# Schematic7.net
KiCad netlist of a schematic drawn in EAGLE
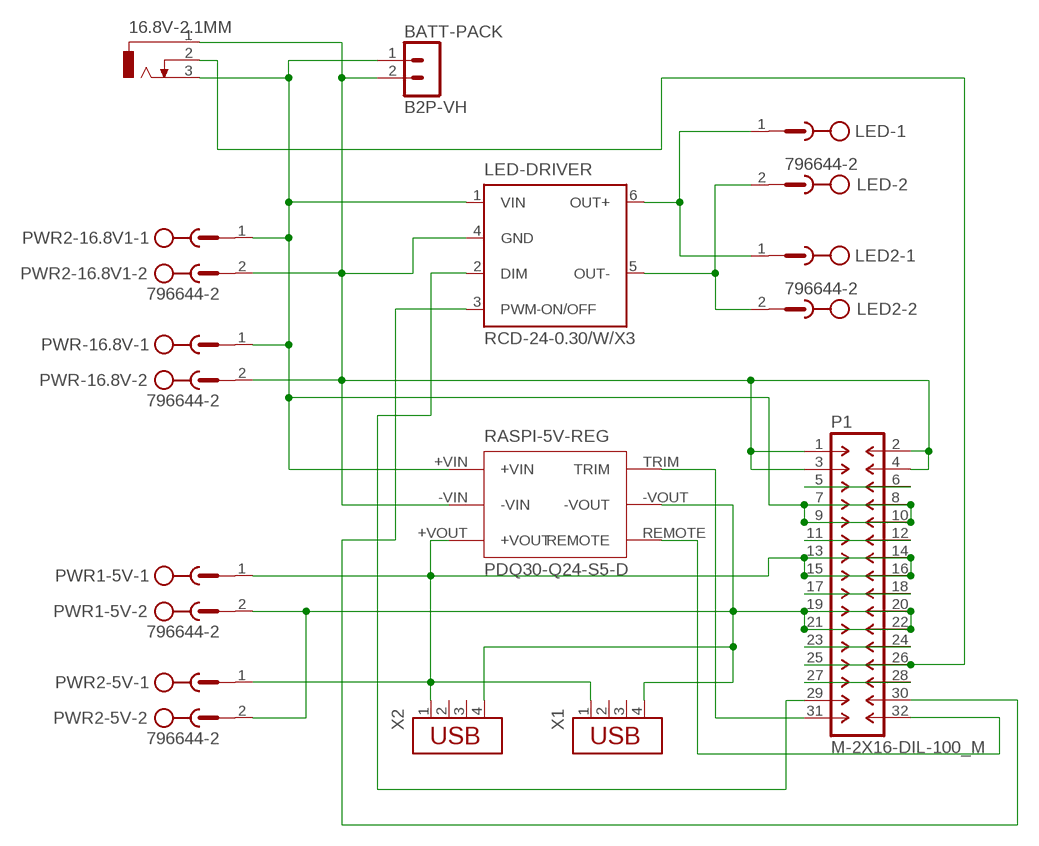
[diagram p0: schematic, sheet 1]

(export (version "E")
  (design (tool "Eeschema 10.0.6"))
  (components
    (comp (ref "16.8V-2.1MM")
      (value "DCJ0303")
      (footprint "eagle-import:DCJ0303")
      (libsource (lib "eagle-import") (part "DCJ0303"))
    )
    (comp (ref "BATT-PACK")
      (value "B2P-VH")
      (footprint "eagle-import:B2P-VH")
      (libsource (lib "eagle-import") (part "B2P-VH"))
    )
    (comp (ref "LED")
      (value "796644-2")
      (footprint "eagle-import:796644-2")
      (libsource (lib "eagle-import") (part "796644-2"))
    )
    (comp (ref "LED-DRIVER")
      (value "RCD-24-0.30/W/X3")
      (footprint "eagle-import:RCD-24_W_X3")
      (libsource (lib "eagle-import") (part "RCD-24/W/X3-0.30"))
    )
    (comp (ref "LED2")
      (value "796644-2")
      (footprint "eagle-import:796644-2")
      (libsource (lib "eagle-import") (part "796644-2"))
    )
    (comp (ref "P1")
      (value "M-2X16-DIL-100_M")
      (footprint "eagle-import:DIL-100-2X16_M")
      (libsource (lib "eagle-import") (part "M-2X16-DIL-100_M"))
    )
    (comp (ref "PWR-16.8V")
      (value "796644-2")
      (footprint "eagle-import:796644-2")
      (libsource (lib "eagle-import") (part "796644-2"))
    )
    (comp (ref "PWR1-5V")
      (value "796644-2")
      (footprint "eagle-import:796644-2")
      (libsource (lib "eagle-import") (part "796644-2"))
    )
    (comp (ref "PWR2-5V")
      (value "796644-2")
      (footprint "eagle-import:796644-2")
      (libsource (lib "eagle-import") (part "796644-2"))
    )
    (comp (ref "PWR2-16.8V1")
      (value "796644-2")
      (footprint "eagle-import:796644-2")
      (libsource (lib "eagle-import") (part "796644-2"))
    )
    (comp (ref "RASPI-5V-REG")
      (value "PDQ30-Q24-S5-D")
      (footprint "eagle-import:PDQ30-Q24-S5-D")
      (libsource (lib "eagle-import") (part "PDQ30-Q24-S5-D"))
    )
    (comp (ref "X1")
      (value "USB-787616")
      (footprint "eagle-import:USB")
      (libsource (lib "eagle-import") (part "USB-787616"))
    )
    (comp (ref "X2")
      (value "USB-787616")
      (footprint "eagle-import:USB")
      (libsource (lib "eagle-import") (part "USB-787616"))
    )
  )
  (nets
    (net (code "1") (name "Net-(16.8V-2.1MM-Pad2)") (class "Default")
      (node (ref "16.8V-2.1MM") (pin "2") (pinfunction "2_2") (pintype "passive"))
      (node (ref "P1") (pin "25") (pinfunction "25_25") (pintype "passive"))
      (node (ref "P1") (pin "26") (pinfunction "26_26") (pintype "passive"))
    )
    (net (code "2") (name "Net-(LED-DRIVER-DIM)") (class "Default")
      (node (ref "LED-DRIVER") (pin "2") (pinfunction "DIM_2") (pintype "passive"))
      (node (ref "P1") (pin "29") (pinfunction "29_29") (pintype "passive"))
    )
    (net (code "3") (name "Net-(LED-DRIVER-GND)") (class "Default")
      (node (ref "16.8V-2.1MM") (pin "1") (pinfunction "1_1") (pintype "passive"))
      (node (ref "BATT-PACK") (pin "2") (pinfunction "2_2") (pintype "passive"))
      (node (ref "LED-DRIVER") (pin "4") (pinfunction "GND_4") (pintype "power_in"))
      (node (ref "P1") (pin "1") (pinfunction "1_1") (pintype "passive"))
      (node (ref "P1") (pin "2") (pinfunction "2_2") (pintype "passive"))
      (node (ref "P1") (pin "3") (pinfunction "3_3") (pintype "passive"))
      (node (ref "P1") (pin "4") (pinfunction "4_4") (pintype "passive"))
      (node (ref "PWR-16.8V") (pin "2") (pinfunction "SK_2") (pintype "passive"))
      (node (ref "PWR2-16.8V1") (pin "2") (pinfunction "SK_2") (pintype "passive"))
      (node (ref "RASPI-5V-REG") (pin "-VIN") (pinfunction "-VIN_-VIN") (pintype "bidirectional"))
    )
    (net (code "4") (name "Net-(LED-DRIVER-OUT+)") (class "Default")
      (node (ref "LED") (pin "1") (pinfunction "SK_1") (pintype "passive"))
      (node (ref "LED-DRIVER") (pin "6") (pinfunction "OUT+_6") (pintype "output"))
      (node (ref "LED2") (pin "1") (pinfunction "SK_1") (pintype "passive"))
    )
    (net (code "5") (name "Net-(LED-DRIVER-OUT-)") (class "Default")
      (node (ref "LED") (pin "2") (pinfunction "SK_2") (pintype "passive"))
      (node (ref "LED-DRIVER") (pin "5") (pinfunction "OUT-_5") (pintype "output"))
      (node (ref "LED2") (pin "2") (pinfunction "SK_2") (pintype "passive"))
    )
    (net (code "6") (name "Net-(LED-DRIVER-PWM-ON{slash}OFF)") (class "Default")
      (node (ref "LED-DRIVER") (pin "3") (pinfunction "PWM-ON/OFF_3") (pintype "passive"))
      (node (ref "P1") (pin "30") (pinfunction "30_30") (pintype "passive"))
    )
    (net (code "7") (name "Net-(LED-DRIVER-VIN)") (class "Default")
      (node (ref "16.8V-2.1MM") (pin "3") (pinfunction "3_3") (pintype "passive"))
      (node (ref "BATT-PACK") (pin "1") (pinfunction "1_1") (pintype "passive"))
      (node (ref "LED-DRIVER") (pin "1") (pinfunction "VIN_1") (pintype "input"))
      (node (ref "P1") (pin "10") (pinfunction "10_10") (pintype "passive"))
      (node (ref "P1") (pin "7") (pinfunction "7_7") (pintype "passive"))
      (node (ref "P1") (pin "8") (pinfunction "8_8") (pintype "passive"))
      (node (ref "P1") (pin "9") (pinfunction "9_9") (pintype "passive"))
      (node (ref "PWR-16.8V") (pin "1") (pinfunction "SK_1") (pintype "passive"))
      (node (ref "PWR2-16.8V1") (pin "1") (pinfunction "SK_1") (pintype "passive"))
      (node (ref "RASPI-5V-REG") (pin "+VIN") (pinfunction "+VIN_+VIN") (pintype "bidirectional"))
    )
    (net (code "8") (name "Net-(P1-Pad5)") (class "Default")
      (node (ref "P1") (pin "5") (pinfunction "5_5") (pintype "passive"))
      (node (ref "P1") (pin "6") (pinfunction "6_6") (pintype "passive"))
    )
    (net (code "9") (name "Net-(P1-Pad11)") (class "Default")
      (node (ref "P1") (pin "11") (pinfunction "11_11") (pintype "passive"))
      (node (ref "P1") (pin "12") (pinfunction "12_12") (pintype "passive"))
    )
    (net (code "10") (name "Net-(P1-Pad17)") (class "Default")
      (node (ref "P1") (pin "17") (pinfunction "17_17") (pintype "passive"))
      (node (ref "P1") (pin "18") (pinfunction "18_18") (pintype "passive"))
    )
    (net (code "11") (name "Net-(P1-Pad23)") (class "Default")
      (node (ref "P1") (pin "23") (pinfunction "23_23") (pintype "passive"))
      (node (ref "P1") (pin "24") (pinfunction "24_24") (pintype "passive"))
    )
    (net (code "12") (name "Net-(P1-Pad27)") (class "Default")
      (node (ref "P1") (pin "27") (pinfunction "27_27") (pintype "passive"))
      (node (ref "P1") (pin "28") (pinfunction "28_28") (pintype "passive"))
    )
    (net (code "13") (name "Net-(P1-Pad31)") (class "Default")
      (node (ref "P1") (pin "31") (pinfunction "31_31") (pintype "passive"))
      (node (ref "RASPI-5V-REG") (pin "TRIM") (pinfunction "TRIM_TRIM") (pintype "bidirectional"))
    )
    (net (code "14") (name "Net-(P1-Pad32)") (class "Default")
      (node (ref "P1") (pin "32") (pinfunction "32_32") (pintype "passive"))
      (node (ref "RASPI-5V-REG") (pin "REMOTE") (pinfunction "REMOTE_REMOTE") (pintype "bidirectional"))
    )
    (net (code "15") (name "Net-(PWR1-5VA-SK)") (class "Default")
      (node (ref "P1") (pin "13") (pinfunction "13_13") (pintype "passive"))
      (node (ref "P1") (pin "14") (pinfunction "14_14") (pintype "passive"))
      (node (ref "P1") (pin "15") (pinfunction "15_15") (pintype "passive"))
      (node (ref "P1") (pin "16") (pinfunction "16_16") (pintype "passive"))
      (node (ref "PWR1-5V") (pin "1") (pinfunction "SK_1") (pintype "passive"))
      (node (ref "PWR2-5V") (pin "1") (pinfunction "SK_1") (pintype "passive"))
      (node (ref "RASPI-5V-REG") (pin "+VOUT") (pinfunction "+VOUT_+VOUT") (pintype "bidirectional"))
      (node (ref "X1") (pin "1") (pinfunction "1_1") (pintype "passive"))
      (node (ref "X2") (pin "1") (pinfunction "1_1") (pintype "passive"))
    )
    (net (code "16") (name "Net-(PWR1-5VB-SK)") (class "Default")
      (node (ref "P1") (pin "19") (pinfunction "19_19") (pintype "passive"))
      (node (ref "P1") (pin "20") (pinfunction "20_20") (pintype "passive"))
      (node (ref "P1") (pin "21") (pinfunction "21_21") (pintype "passive"))
      (node (ref "P1") (pin "22") (pinfunction "22_22") (pintype "passive"))
      (node (ref "PWR1-5V") (pin "2") (pinfunction "SK_2") (pintype "passive"))
      (node (ref "PWR2-5V") (pin "2") (pinfunction "SK_2") (pintype "passive"))
      (node (ref "RASPI-5V-REG") (pin "-VOUT") (pinfunction "-VOUT_-VOUT") (pintype "bidirectional"))
      (node (ref "X1") (pin "4") (pinfunction "4_4") (pintype "passive"))
      (node (ref "X2") (pin "4") (pinfunction "4_4") (pintype "passive"))
    )
    (net (code "17") (name "unconnected-(X1-Pad2)") (class "Default")
      (node (ref "X1") (pin "2") (pinfunction "2_2") (pintype "passive"))
    )
    (net (code "18") (name "unconnected-(X1-Pad3)") (class "Default")
      (node (ref "X1") (pin "3") (pinfunction "3_3") (pintype "passive"))
    )
    (net (code "19") (name "unconnected-(X2-Pad2)") (class "Default")
      (node (ref "X2") (pin "2") (pinfunction "2_2") (pintype "passive"))
    )
    (net (code "20") (name "unconnected-(X2-Pad3)") (class "Default")
      (node (ref "X2") (pin "3") (pinfunction "3_3") (pintype "passive"))
    )
  )
)
